# reciever_pcb.net
KiCad netlist of a schematic drawn in EAGLE
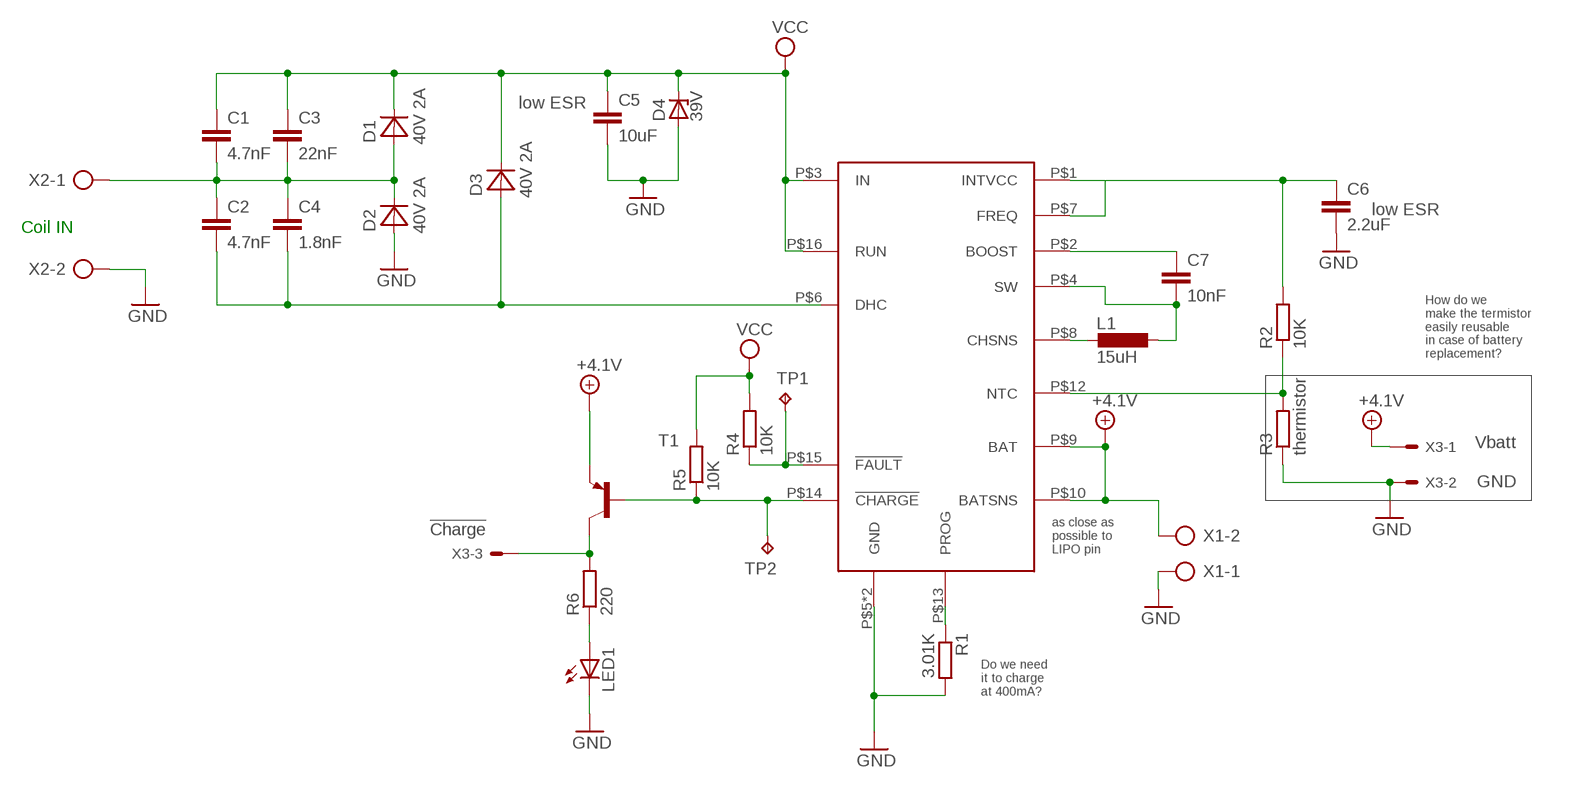
[diagram p0: schematic, sheet 1]

(export (version "E")
  (design (tool "Eeschema 10.0.6"))
  (components
    (comp (ref "C1")
      (value "4.7nF")
      (footprint "eagle-import:C0805")
      (libsource (lib "eagle-import") (part "C-EUC0805"))
    )
    (comp (ref "C2")
      (value "4.7nF")
      (footprint "eagle-import:C0805")
      (libsource (lib "eagle-import") (part "C-EUC0805"))
    )
    (comp (ref "C3")
      (value "22nF")
      (footprint "eagle-import:C0805")
      (libsource (lib "eagle-import") (part "C-EUC0805"))
    )
    (comp (ref "C4")
      (value "1.8nF")
      (footprint "eagle-import:C0805")
      (libsource (lib "eagle-import") (part "C-EUC0805"))
    )
    (comp (ref "C5")
      (value "10uF")
      (footprint "eagle-import:C0805")
      (libsource (lib "eagle-import") (part "C-EUC0805"))
    )
    (comp (ref "C6")
      (value "2.2uF")
      (footprint "eagle-import:C0805")
      (libsource (lib "eagle-import") (part "C-EUC0805"))
    )
    (comp (ref "C7")
      (value "10nF")
      (footprint "eagle-import:C0805")
      (libsource (lib "eagle-import") (part "C-EUC0805"))
    )
    (comp (ref "D1")
      (value "40V 2A")
      (footprint "eagle-import:SMA")
      (libsource (lib "eagle-import") (part "MBRA340T3"))
    )
    (comp (ref "D2")
      (value "40V 2A")
      (footprint "eagle-import:SMA")
      (libsource (lib "eagle-import") (part "MBRA340T3"))
    )
    (comp (ref "D3")
      (value "40V 2A")
      (footprint "eagle-import:SMA")
      (libsource (lib "eagle-import") (part "MBRA340T3"))
    )
    (comp (ref "D4")
      (value "39V")
      (footprint "eagle-import:SMB")
      (libsource (lib "eagle-import") (part "ZENER-DIODESMB"))
    )
    (comp (ref "L1")
      (value "15uH")
      (footprint "eagle-import:L1812")
      (libsource (lib "eagle-import") (part "L-EUL1812"))
    )
    (comp (ref "LED1")
      (value "LEDCHIP-LED0805")
      (footprint "eagle-import:CHIP-LED0805")
      (libsource (lib "eagle-import") (part "LEDCHIP-LED0805"))
    )
    (comp (ref "R1")
      (value "3.01K")
      (footprint "eagle-import:R0805")
      (libsource (lib "eagle-import") (part "R-EU_R0805"))
    )
    (comp (ref "R2")
      (value "10K")
      (footprint "eagle-import:R0805")
      (libsource (lib "eagle-import") (part "R-EU_R0805"))
    )
    (comp (ref "R3")
      (value "thermistor")
      (footprint "eagle-import:0207_2V")
      (libsource (lib "eagle-import") (part "R-EU_0207/2V"))
    )
    (comp (ref "R4")
      (value "10K")
      (footprint "eagle-import:R0805")
      (libsource (lib "eagle-import") (part "R-EU_R0805"))
    )
    (comp (ref "R5")
      (value "10K")
      (footprint "eagle-import:R0805")
      (libsource (lib "eagle-import") (part "R-EU_R0805"))
    )
    (comp (ref "R6")
      (value "220")
      (footprint "eagle-import:R0805")
      (libsource (lib "eagle-import") (part "R-EU_R0805"))
    )
    (comp (ref "T1")
      (value "-PNP-SOT23-BCE")
      (footprint "eagle-import:SOT23-BCE")
      (libsource (lib "eagle-import") (part "-PNP-SOT23-BCE"))
    )
    (comp (ref "TP1")
      (value "TPTP19R")
      (footprint "eagle-import:TP19R")
      (libsource (lib "eagle-import") (part "TPTP19R"))
    )
    (comp (ref "TP2")
      (value "TPTP19R")
      (footprint "eagle-import:TP19R")
      (libsource (lib "eagle-import") (part "TPTP19R"))
    )
    (comp (ref "U$1")
      (value "LT4120")
      (footprint "eagle-import:QFN16")
      (libsource (lib "eagle-import") (part "LT4120"))
    )
    (comp (ref "X1")
      (value "AK500/2")
      (footprint "eagle-import:AK500_2")
      (libsource (lib "eagle-import") (part "AK500/2"))
    )
    (comp (ref "X2")
      (value "AK500/2")
      (footprint "eagle-import:AK500_2")
      (libsource (lib "eagle-import") (part "AK500/2"))
    )
    (comp (ref "X3")
      (value "KK-156-3")
      (footprint "eagle-import:KK-156-3")
      (libsource (lib "eagle-import") (part "KK-156-3"))
    )
  )
  (nets
    (net (code "1") (name "+4.1V") (class "Default")
      (node (ref "T1") (pin "E") (pinfunction "E_E") (pintype "passive"))
      (node (ref "U$1") (pin "P$10") (pinfunction "BATSNS_P$10") (pintype "bidirectional"))
      (node (ref "U$1") (pin "P$9") (pinfunction "BAT_P$9") (pintype "bidirectional"))
      (node (ref "X1") (pin "2") (pinfunction "KL_2") (pintype "passive"))
      (node (ref "X3") (pin "1") (pinfunction "S_1") (pintype "passive"))
    )
    (net (code "2") (name "GND") (class "Default")
      (node (ref "C5") (pin "2") (pinfunction "2_2") (pintype "passive"))
      (node (ref "C6") (pin "2") (pinfunction "2_2") (pintype "passive"))
      (node (ref "D2") (pin "A") (pinfunction "A_A") (pintype "passive"))
      (node (ref "D4") (pin "A") (pinfunction "A_A") (pintype "passive"))
      (node (ref "LED1") (pin "C") (pinfunction "C_C") (pintype "passive"))
      (node (ref "R1") (pin "2") (pinfunction "2_2") (pintype "passive"))
      (node (ref "R3") (pin "1") (pinfunction "1_1") (pintype "passive"))
      (node (ref "U$1") (pin "P$17") (pinfunction "GND_P$17") (pintype "power_in"))
      (node (ref "U$1") (pin "P$5") (pinfunction "GND_P$5") (pintype "power_in"))
      (node (ref "X1") (pin "1") (pinfunction "KL_1") (pintype "passive"))
      (node (ref "X2") (pin "2") (pinfunction "KL_2") (pintype "passive"))
      (node (ref "X3") (pin "2") (pinfunction "S_2") (pintype "passive"))
    )
    (net (code "3") (name "Net-(C2-Pad2)") (class "Default")
      (node (ref "C2") (pin "2") (pinfunction "2_2") (pintype "passive"))
      (node (ref "C4") (pin "2") (pinfunction "2_2") (pintype "passive"))
      (node (ref "D3") (pin "A") (pinfunction "A_A") (pintype "passive"))
    )
    (net (code "4") (name "Net-(LED1-PadA)") (class "Default")
      (node (ref "LED1") (pin "A") (pinfunction "A_A") (pintype "passive"))
      (node (ref "R6") (pin "1") (pinfunction "1_1") (pintype "passive"))
    )
    (net (code "5") (name "Net-(U$1-BOOST)") (class "Default")
      (node (ref "C7") (pin "1") (pinfunction "1_1") (pintype "passive"))
      (node (ref "U$1") (pin "P$2") (pinfunction "BOOST_P$2") (pintype "bidirectional"))
    )
    (net (code "6") (name "Net-(U$1-CHSNS)") (class "Default")
      (node (ref "L1") (pin "2") (pinfunction "2_2") (pintype "passive"))
      (node (ref "U$1") (pin "P$8") (pinfunction "CHSNS_P$8") (pintype "bidirectional"))
    )
    (net (code "7") (name "Net-(U$1-FREQ)") (class "Default")
      (node (ref "C6") (pin "1") (pinfunction "1_1") (pintype "passive"))
      (node (ref "R2") (pin "2") (pinfunction "2_2") (pintype "passive"))
      (node (ref "U$1") (pin "P$1") (pinfunction "INTVCC_P$1") (pintype "bidirectional"))
      (node (ref "U$1") (pin "P$7") (pinfunction "FREQ_P$7") (pintype "bidirectional"))
    )
    (net (code "8") (name "Net-(U$1-NTC)") (class "Default")
      (node (ref "R2") (pin "1") (pinfunction "1_1") (pintype "passive"))
      (node (ref "R3") (pin "2") (pinfunction "2_2") (pintype "passive"))
      (node (ref "U$1") (pin "P$12") (pinfunction "NTC_P$12") (pintype "bidirectional"))
    )
    (net (code "9") (name "Net-(U$1-PROG)") (class "Default")
      (node (ref "R1") (pin "1") (pinfunction "1_1") (pintype "passive"))
      (node (ref "U$1") (pin "P$13") (pinfunction "PROG_P$13") (pintype "bidirectional"))
    )
    (net (code "10") (name "Net-(U$1-SW)") (class "Default")
      (node (ref "C7") (pin "2") (pinfunction "2_2") (pintype "passive"))
      (node (ref "L1") (pin "1") (pinfunction "1_1") (pintype "passive"))
      (node (ref "U$1") (pin "P$4") (pinfunction "SW_P$4") (pintype "bidirectional"))
    )
    (net (code "11") (name "Net-(U$1-~{CHARGE})") (class "Default")
      (node (ref "R5") (pin "1") (pinfunction "1_1") (pintype "passive"))
      (node (ref "T1") (pin "B") (pinfunction "B_B") (pintype "passive"))
      (node (ref "TP2") (pin "TP") (pinfunction "TP_TP") (pintype "input"))
      (node (ref "U$1") (pin "P$14") (pinfunction "~{CHARGE}_P$14") (pintype "bidirectional"))
    )
    (net (code "12") (name "Net-(U$1-~{FAULT})") (class "Default")
      (node (ref "R4") (pin "1") (pinfunction "1_1") (pintype "passive"))
      (node (ref "TP1") (pin "TP") (pinfunction "TP_TP") (pintype "input"))
      (node (ref "U$1") (pin "P$15") (pinfunction "~{FAULT}_P$15") (pintype "bidirectional"))
    )
    (net (code "13") (name "Net-(X2A-KL)") (class "Default")
      (node (ref "C1") (pin "2") (pinfunction "2_2") (pintype "passive"))
      (node (ref "C2") (pin "1") (pinfunction "1_1") (pintype "passive"))
      (node (ref "C3") (pin "2") (pinfunction "2_2") (pintype "passive"))
      (node (ref "C4") (pin "1") (pinfunction "1_1") (pintype "passive"))
      (node (ref "D1") (pin "A") (pinfunction "A_A") (pintype "passive"))
      (node (ref "D2") (pin "C") (pinfunction "C_C") (pintype "passive"))
      (node (ref "X2") (pin "1") (pinfunction "KL_1") (pintype "passive"))
    )
    (net (code "14") (name "Net-(X3C-S)") (class "Default")
      (node (ref "R6") (pin "2") (pinfunction "2_2") (pintype "passive"))
      (node (ref "T1") (pin "C") (pinfunction "C_C") (pintype "passive"))
      (node (ref "X3") (pin "3") (pinfunction "S_3") (pintype "passive"))
    )
    (net (code "15") (name "VCC") (class "Default")
      (node (ref "C1") (pin "1") (pinfunction "1_1") (pintype "passive"))
      (node (ref "C3") (pin "1") (pinfunction "1_1") (pintype "passive"))
      (node (ref "C5") (pin "1") (pinfunction "1_1") (pintype "passive"))
      (node (ref "D1") (pin "C") (pinfunction "C_C") (pintype "passive"))
      (node (ref "D3") (pin "C") (pinfunction "C_C") (pintype "passive"))
      (node (ref "D4") (pin "C") (pinfunction "C_C") (pintype "passive"))
      (node (ref "R4") (pin "2") (pinfunction "2_2") (pintype "passive"))
      (node (ref "R5") (pin "2") (pinfunction "2_2") (pintype "passive"))
      (node (ref "U$1") (pin "P$16") (pinfunction "RUN_P$16") (pintype "bidirectional"))
      (node (ref "U$1") (pin "P$3") (pinfunction "IN_P$3") (pintype "power_in"))
    )
    (net (code "16") (name "unconnected-(U$1-DHC-PadP$6)") (class "Default")
      (node (ref "U$1") (pin "P$6") (pinfunction "DHC_P$6") (pintype "bidirectional"))
    )
  )
)
